# c200_rev_a.net
KiCad netlist of a schematic drawn in EAGLE
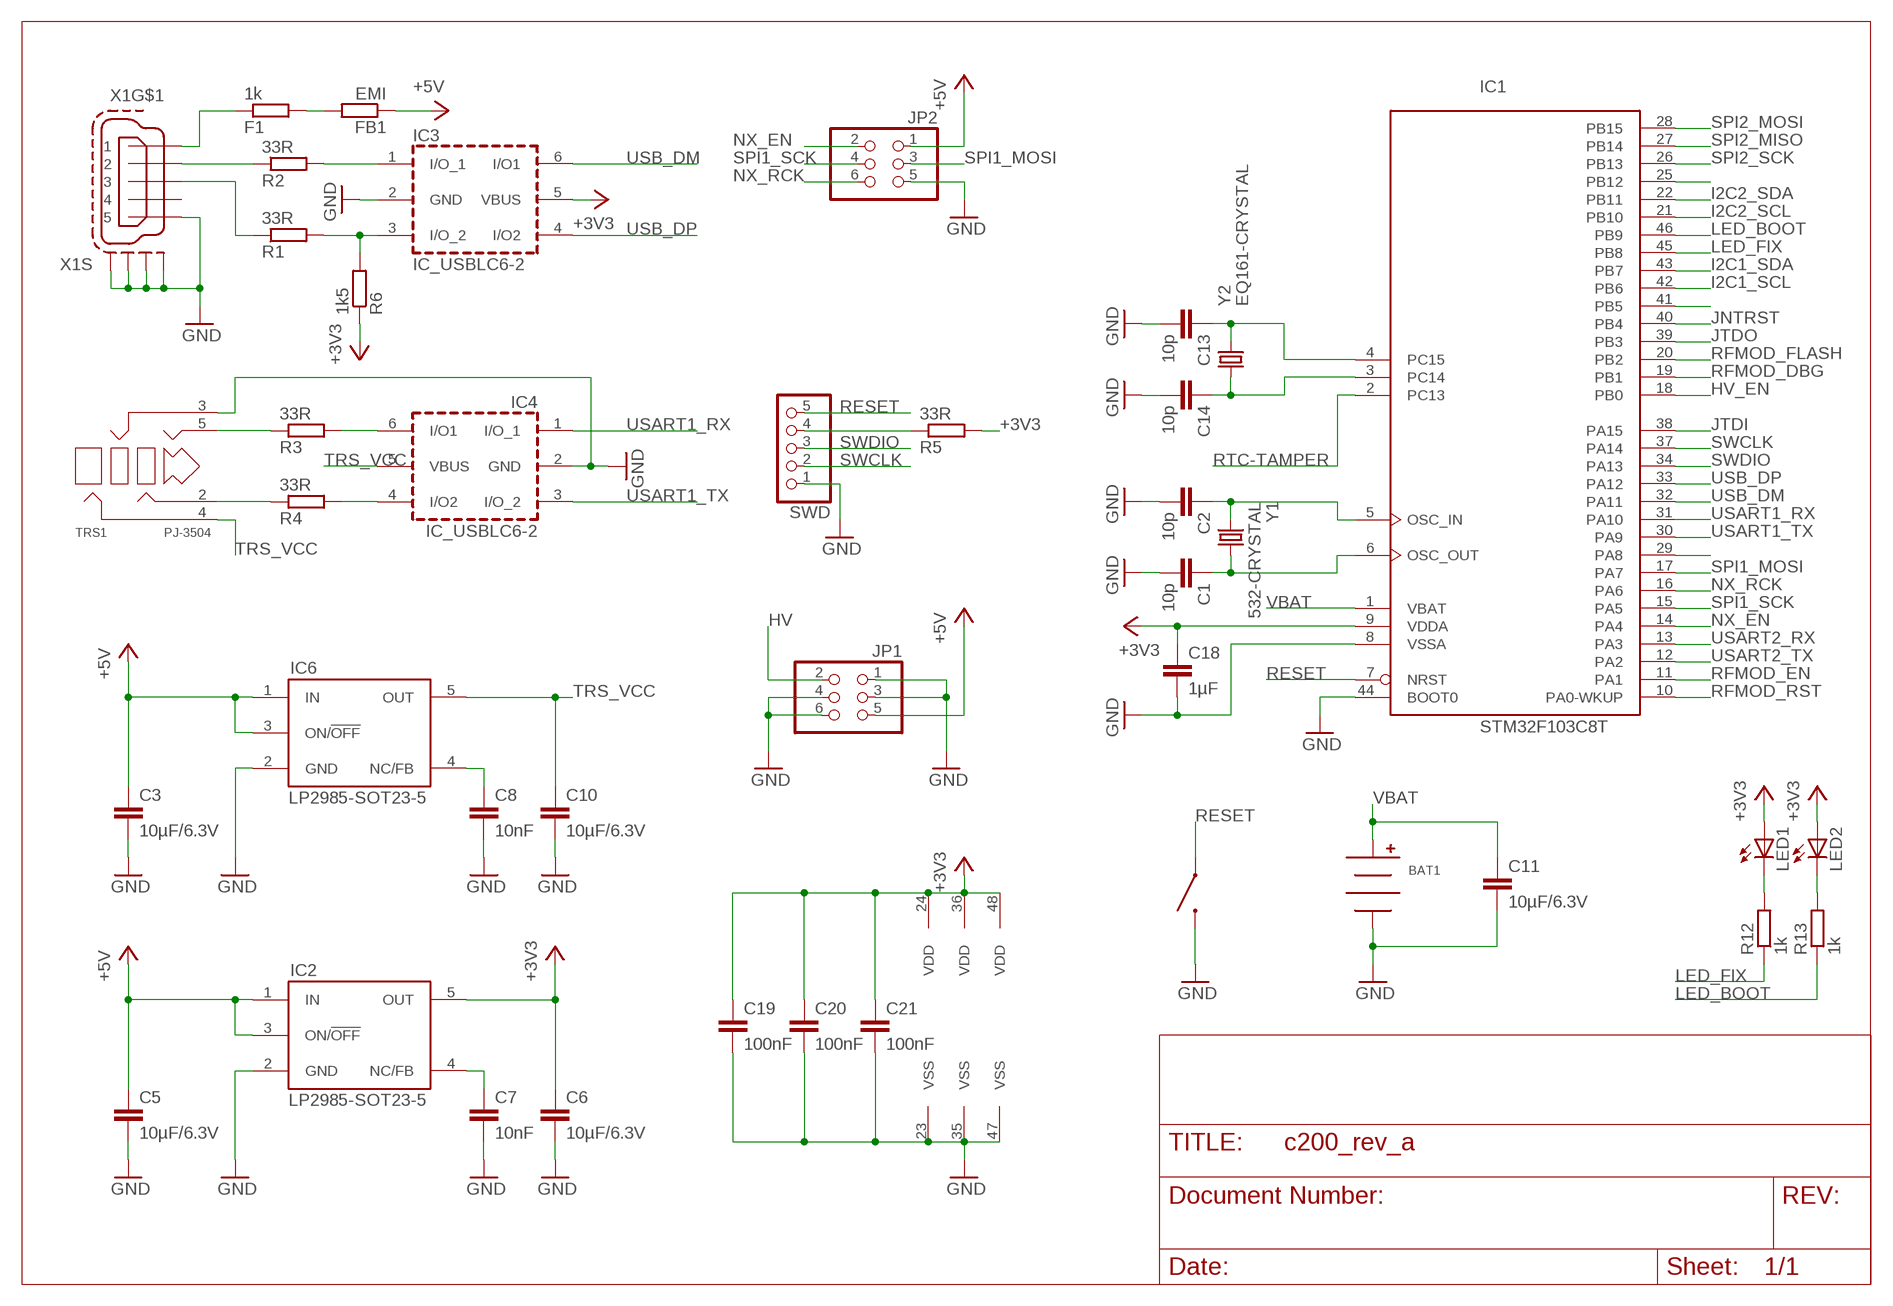
[diagram p0: schematic, sheet 1, part 1 of 2]
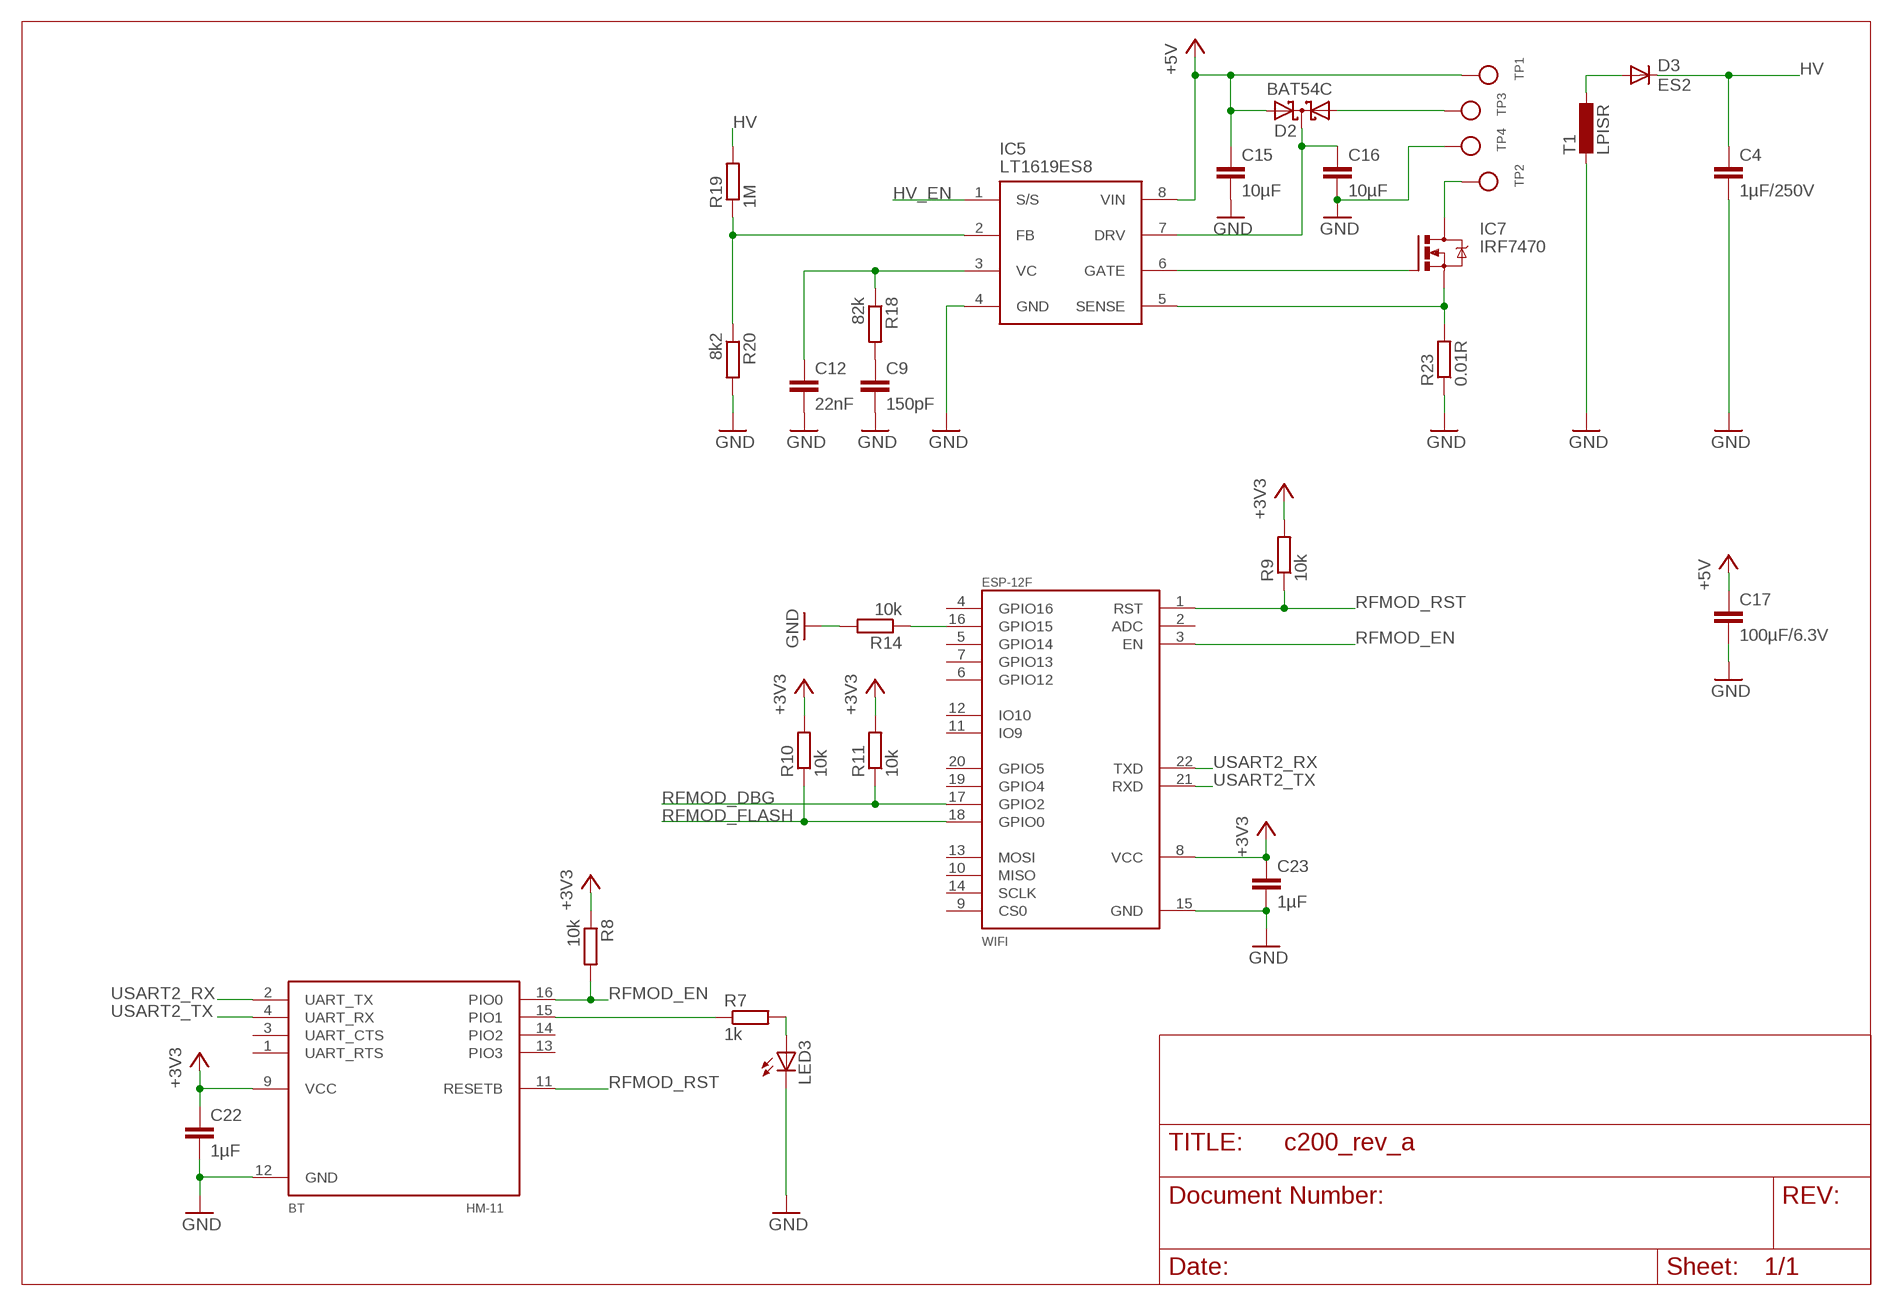
[diagram p1: schematic, sheet 1, part 2 of 2]

(export (version "E")
  (design (tool "Eeschema 10.0.6"))
  (components
    (comp (ref "BAT1")
      (value "CR1220-HOLDER")
      (footprint "eagle-import:HARWIN-CR1220")
      (libsource (lib "eagle-import") (part "CR1220-HOLDER"))
    )
    (comp (ref "BT")
      (value "HM-11")
      (footprint "eagle-import:HM-11")
      (libsource (lib "eagle-import") (part "HM-11"))
    )
    (comp (ref "C1")
      (value "10p")
      (footprint "eagle-import:C0603")
      (libsource (lib "eagle-import") (part "C-EUC0603"))
    )
    (comp (ref "C2")
      (value "10p")
      (footprint "eagle-import:C0603")
      (libsource (lib "eagle-import") (part "C-EUC0603"))
    )
    (comp (ref "C3")
      (value "10µF/6.3V")
      (footprint "eagle-import:C0603")
      (libsource (lib "eagle-import") (part "C-EUC0603"))
    )
    (comp (ref "C4")
      (value "1µF/250V")
      (footprint "eagle-import:C2220K")
      (libsource (lib "eagle-import") (part "C-EUC2220K"))
    )
    (comp (ref "C5")
      (value "10µF/6.3V")
      (footprint "eagle-import:C0603")
      (libsource (lib "eagle-import") (part "C-EUC0603"))
    )
    (comp (ref "C6")
      (value "10µF/6.3V")
      (footprint "eagle-import:C0603")
      (libsource (lib "eagle-import") (part "C-EUC0603"))
    )
    (comp (ref "C7")
      (value "10nF")
      (footprint "eagle-import:C0603")
      (libsource (lib "eagle-import") (part "C-EUC0603"))
    )
    (comp (ref "C8")
      (value "10nF")
      (footprint "eagle-import:C0603")
      (libsource (lib "eagle-import") (part "C-EUC0603"))
    )
    (comp (ref "C9")
      (value "150pF")
      (footprint "eagle-import:C0603")
      (libsource (lib "eagle-import") (part "C-EUC0603"))
    )
    (comp (ref "C10")
      (value "10µF/6.3V")
      (footprint "eagle-import:C0603")
      (libsource (lib "eagle-import") (part "C-EUC0603"))
    )
    (comp (ref "C11")
      (value "10µF/6.3V")
      (footprint "eagle-import:C0603")
      (libsource (lib "eagle-import") (part "C-EUC0603"))
    )
    (comp (ref "C12")
      (value "22nF")
      (footprint "eagle-import:C0603")
      (libsource (lib "eagle-import") (part "C-EUC0603"))
    )
    (comp (ref "C13")
      (value "10p")
      (footprint "eagle-import:C0603")
      (libsource (lib "eagle-import") (part "C-EUC0603"))
    )
    (comp (ref "C14")
      (value "10p")
      (footprint "eagle-import:C0603")
      (libsource (lib "eagle-import") (part "C-EUC0603"))
    )
    (comp (ref "C15")
      (value "10µF")
      (footprint "eagle-import:C0603")
      (libsource (lib "eagle-import") (part "C-EUC0603"))
    )
    (comp (ref "C16")
      (value "10µF")
      (footprint "eagle-import:C0603")
      (libsource (lib "eagle-import") (part "C-EUC0603"))
    )
    (comp (ref "C17")
      (value "100µF/6.3V")
      (footprint "eagle-import:C1210")
      (libsource (lib "eagle-import") (part "C-EUC1210"))
    )
    (comp (ref "C18")
      (value "1µF")
      (footprint "eagle-import:C0603")
      (libsource (lib "eagle-import") (part "C-EUC0603"))
    )
    (comp (ref "C19")
      (value "100nF")
      (footprint "eagle-import:C0603")
      (libsource (lib "eagle-import") (part "C-EUC0603"))
    )
    (comp (ref "C20")
      (value "100nF")
      (footprint "eagle-import:C0603")
      (libsource (lib "eagle-import") (part "C-EUC0603"))
    )
    (comp (ref "C21")
      (value "100nF")
      (footprint "eagle-import:C0603")
      (libsource (lib "eagle-import") (part "C-EUC0603"))
    )
    (comp (ref "C22")
      (value "1µF")
      (footprint "eagle-import:C0603")
      (libsource (lib "eagle-import") (part "C-EUC0603"))
    )
    (comp (ref "C23")
      (value "1µF")
      (footprint "eagle-import:C0603")
      (libsource (lib "eagle-import") (part "C-EUC0603"))
    )
    (comp (ref "D2")
      (value "BAT54C")
      (footprint "eagle-import:SOT23")
      (libsource (lib "eagle-import") (part "BAT54C"))
    )
    (comp (ref "D3")
      (value "ES2")
      (footprint "eagle-import:DO-214AA")
      (libsource (lib "eagle-import") (part "ES2"))
    )
    (comp (ref "F1")
      (value "1k")
      (footprint "eagle-import:R0603")
      (libsource (lib "eagle-import") (part "R-EU_R0603"))
    )
    (comp (ref "FB1")
      (value "EMI")
      (footprint "eagle-import:R0603")
      (libsource (lib "eagle-import") (part "R-EU_R0603"))
    )
    (comp (ref "IC1")
      (value "STM32F103C8T")
      (footprint "eagle-import:LQFP48")
      (libsource (lib "eagle-import") (part "STM32F103CT8"))
    )
    (comp (ref "IC2")
      (value "LP2985-SOT23-5")
      (footprint "eagle-import:SOT23-5")
      (libsource (lib "eagle-import") (part "LP2985-SOT23-5"))
    )
    (comp (ref "IC3")
      (value "IC_USBLC6-2")
      (footprint "eagle-import:SOT-23-6L")
      (libsource (lib "eagle-import") (part "IC_USBLC6-2"))
    )
    (comp (ref "IC4")
      (value "IC_USBLC6-2")
      (footprint "eagle-import:SOT-23-6L")
      (libsource (lib "eagle-import") (part "IC_USBLC6-2"))
    )
    (comp (ref "IC5")
      (value "LT1619ES8")
      (footprint "eagle-import:SO8")
      (libsource (lib "eagle-import") (part "LT1619ES8"))
    )
    (comp (ref "IC6")
      (value "LP2985-SOT23-5")
      (footprint "eagle-import:SOT23-5")
      (libsource (lib "eagle-import") (part "LP2985-SOT23-5"))
    )
    (comp (ref "IC7")
      (value "IRF7470")
      (footprint "eagle-import:SO8")
      (libsource (lib "eagle-import") (part "IRF7470"))
    )
    (comp (ref "ISP")
      (value "TACT-SWITCH-40-40")
      (footprint "eagle-import:40-40")
      (libsource (lib "eagle-import") (part "TACT-SWITCH-40-40"))
    )
    (comp (ref "JP1")
      (value "PINHD-2X3_2.54-SMD")
      (footprint "eagle-import:2X03SMD")
      (libsource (lib "eagle-import") (part "PINHD-2X3_2.54-SMD"))
    )
    (comp (ref "JP2")
      (value "PINHD-2X3_2.54-SMD")
      (footprint "eagle-import:2X03SMD")
      (libsource (lib "eagle-import") (part "PINHD-2X3_2.54-SMD"))
    )
    (comp (ref "LED1")
      (value "LEDCHIP-LED0603")
      (footprint "eagle-import:CHIP-LED0603")
      (libsource (lib "eagle-import") (part "LEDCHIP-LED0603"))
    )
    (comp (ref "LED2")
      (value "LEDCHIP-LED0603")
      (footprint "eagle-import:CHIP-LED0603")
      (libsource (lib "eagle-import") (part "LEDCHIP-LED0603"))
    )
    (comp (ref "LED3")
      (value "LEDCHIP-LED0603")
      (footprint "eagle-import:CHIP-LED0603")
      (libsource (lib "eagle-import") (part "LEDCHIP-LED0603"))
    )
    (comp (ref "R1")
      (value "33R")
      (footprint "eagle-import:R0603")
      (libsource (lib "eagle-import") (part "R-EU_R0603"))
    )
    (comp (ref "R2")
      (value "33R")
      (footprint "eagle-import:R0603")
      (libsource (lib "eagle-import") (part "R-EU_R0603"))
    )
    (comp (ref "R3")
      (value "33R")
      (footprint "eagle-import:R0603")
      (libsource (lib "eagle-import") (part "R-EU_R0603"))
    )
    (comp (ref "R4")
      (value "33R")
      (footprint "eagle-import:R0603")
      (libsource (lib "eagle-import") (part "R-EU_R0603"))
    )
    (comp (ref "R5")
      (value "33R")
      (footprint "eagle-import:R0603")
      (libsource (lib "eagle-import") (part "R-EU_R0603"))
    )
    (comp (ref "R6")
      (value "1k5")
      (footprint "eagle-import:R0603")
      (libsource (lib "eagle-import") (part "R-EU_R0603"))
    )
    (comp (ref "R7")
      (value "1k")
      (footprint "eagle-import:R0603")
      (libsource (lib "eagle-import") (part "R-EU_R0603"))
    )
    (comp (ref "R8")
      (value "10k")
      (footprint "eagle-import:R0603")
      (libsource (lib "eagle-import") (part "R-EU_R0603"))
    )
    (comp (ref "R9")
      (value "10k")
      (footprint "eagle-import:R0603")
      (libsource (lib "eagle-import") (part "R-EU_R0603"))
    )
    (comp (ref "R10")
      (value "10k")
      (footprint "eagle-import:R0603")
      (libsource (lib "eagle-import") (part "R-EU_R0603"))
    )
    (comp (ref "R11")
      (value "10k")
      (footprint "eagle-import:R0603")
      (libsource (lib "eagle-import") (part "R-EU_R0603"))
    )
    (comp (ref "R12")
      (value "1k")
      (footprint "eagle-import:R0603")
      (libsource (lib "eagle-import") (part "R-EU_R0603"))
    )
    (comp (ref "R13")
      (value "1k")
      (footprint "eagle-import:R0603")
      (libsource (lib "eagle-import") (part "R-EU_R0603"))
    )
    (comp (ref "R14")
      (value "10k")
      (footprint "eagle-import:R0603")
      (libsource (lib "eagle-import") (part "R-EU_R0603"))
    )
    (comp (ref "R18")
      (value "82k")
      (footprint "eagle-import:R0603")
      (libsource (lib "eagle-import") (part "R-EU_R0603"))
    )
    (comp (ref "R19")
      (value "1M")
      (footprint "eagle-import:M1206")
      (libsource (lib "eagle-import") (part "R-EU_M1206"))
    )
    (comp (ref "R20")
      (value "8k2")
      (footprint "eagle-import:R0603")
      (libsource (lib "eagle-import") (part "R-EU_R0603"))
    )
    (comp (ref "R23")
      (value "0.01R")
      (footprint "eagle-import:R1206")
      (libsource (lib "eagle-import") (part "R-EU_R1206"))
    )
    (comp (ref "SWD")
      (value "HEADER-1X5ROUND")
      (footprint "eagle-import:1X05_ROUND")
      (libsource (lib "eagle-import") (part "HEADER-1X5ROUND"))
    )
    (comp (ref "T1")
      (value "LPISR")
      (footprint "eagle-import:PISR")
      (libsource (lib "eagle-import") (part "LPISR"))
    )
    (comp (ref "TP1")
      (value "TESTPOINTROUND2MM")
      (footprint "eagle-import:TESTPOINT_ROUND_2MM")
      (libsource (lib "eagle-import") (part "TESTPOINTROUND2MM"))
    )
    (comp (ref "TP2")
      (value "TESTPOINTROUND2MM")
      (footprint "eagle-import:TESTPOINT_ROUND_2MM")
      (libsource (lib "eagle-import") (part "TESTPOINTROUND2MM"))
    )
    (comp (ref "TP3")
      (value "TESTPOINTROUND2MM")
      (footprint "eagle-import:TESTPOINT_ROUND_2MM")
      (libsource (lib "eagle-import") (part "TESTPOINTROUND2MM"))
    )
    (comp (ref "TP4")
      (value "TESTPOINTROUND2MM")
      (footprint "eagle-import:TESTPOINT_ROUND_2MM")
      (libsource (lib "eagle-import") (part "TESTPOINTROUND2MM"))
    )
    (comp (ref "TRS1")
      (value "PJ-3504")
      (footprint "eagle-import:YD-PJ-3504")
      (libsource (lib "eagle-import") (part "PJ-3504"))
    )
    (comp (ref "WIFI")
      (value "ESP-12F")
      (footprint "eagle-import:ESP-12F")
      (libsource (lib "eagle-import") (part "ESP-12F"))
    )
    (comp (ref "X1")
      (value "MINI-USB-SCHIELD-32005-201")
      (footprint "eagle-import:32005-201")
      (libsource (lib "eagle-import") (part "MINI-USB-SCHIELD-32005-201"))
    )
    (comp (ref "Y1")
      (value "532-CRYSTAL")
      (footprint "eagle-import:2PIN50X32")
      (libsource (lib "eagle-import") (part "532-CRYSTAL"))
    )
    (comp (ref "Y2")
      (value "EQ161-CRYSTAL")
      (footprint "eagle-import:EQ161")
      (libsource (lib "eagle-import") (part "EQ161-CRYSTAL"))
    )
  )
  (nets
    (net (code "1") (name "+3V3") (class "Default")
      (node (ref "BT") (pin "9") (pinfunction "VCC_9") (pintype "bidirectional"))
      (node (ref "C18") (pin "1") (pinfunction "1_1") (pintype "passive"))
      (node (ref "C19") (pin "1") (pinfunction "1_1") (pintype "passive"))
      (node (ref "C20") (pin "1") (pinfunction "1_1") (pintype "passive"))
      (node (ref "C21") (pin "1") (pinfunction "1_1") (pintype "passive"))
      (node (ref "C22") (pin "1") (pinfunction "1_1") (pintype "passive"))
      (node (ref "C23") (pin "1") (pinfunction "1_1") (pintype "passive"))
      (node (ref "C6") (pin "1") (pinfunction "1_1") (pintype "passive"))
      (node (ref "IC1") (pin "24") (pinfunction "VDD_24") (pintype "power_in"))
      (node (ref "IC1") (pin "36") (pinfunction "VDD_36") (pintype "power_in"))
      (node (ref "IC1") (pin "48") (pinfunction "VDD_48") (pintype "power_in"))
      (node (ref "IC1") (pin "9") (pinfunction "VDDA_9") (pintype "power_in"))
      (node (ref "IC2") (pin "5") (pinfunction "OUT_5") (pintype "bidirectional"))
      (node (ref "IC3") (pin "5") (pinfunction "VBUS_5") (pintype "bidirectional"))
      (node (ref "LED1") (pin "A") (pinfunction "A_A") (pintype "passive"))
      (node (ref "LED2") (pin "A") (pinfunction "A_A") (pintype "passive"))
      (node (ref "R10") (pin "2") (pinfunction "2_2") (pintype "passive"))
      (node (ref "R11") (pin "2") (pinfunction "2_2") (pintype "passive"))
      (node (ref "R5") (pin "2") (pinfunction "2_2") (pintype "passive"))
      (node (ref "R6") (pin "1") (pinfunction "1_1") (pintype "passive"))
      (node (ref "R8") (pin "1") (pinfunction "1_1") (pintype "passive"))
      (node (ref "R9") (pin "2") (pinfunction "2_2") (pintype "passive"))
      (node (ref "WIFI") (pin "8") (pinfunction "VCC_8") (pintype "bidirectional"))
    )
    (net (code "2") (name "+5V") (class "Default")
      (node (ref "C15") (pin "1") (pinfunction "1_1") (pintype "passive"))
      (node (ref "C17") (pin "1") (pinfunction "1_1") (pintype "passive"))
      (node (ref "C3") (pin "1") (pinfunction "1_1") (pintype "passive"))
      (node (ref "C5") (pin "1") (pinfunction "1_1") (pintype "passive"))
      (node (ref "D2") (pin "2") (pinfunction "A2_2") (pintype "passive"))
      (node (ref "FB1") (pin "1") (pinfunction "1_1") (pintype "passive"))
      (node (ref "IC2") (pin "1") (pinfunction "IN_1") (pintype "bidirectional"))
      (node (ref "IC2") (pin "3") (pinfunction "ON/~{OFF}_3") (pintype "bidirectional"))
      (node (ref "IC5") (pin "8") (pinfunction "VIN_8") (pintype "bidirectional"))
      (node (ref "IC6") (pin "1") (pinfunction "IN_1") (pintype "bidirectional"))
      (node (ref "IC6") (pin "3") (pinfunction "ON/~{OFF}_3") (pintype "bidirectional"))
      (node (ref "JP1") (pin "5") (pinfunction "5_5") (pintype "passive"))
      (node (ref "JP2") (pin "1") (pinfunction "1_1") (pintype "passive"))
      (node (ref "TP1") (pin "P$1") (pinfunction "P$1_P$1") (pintype "bidirectional"))
    )
    (net (code "3") (name "/HV") (class "Default")
      (node (ref "C4") (pin "1") (pinfunction "1_1") (pintype "passive"))
      (node (ref "D3") (pin "C") (pinfunction "C_C") (pintype "passive"))
      (node (ref "JP1") (pin "2") (pinfunction "2_2") (pintype "passive"))
      (node (ref "R19") (pin "2") (pinfunction "2_2") (pintype "passive"))
    )
    (net (code "4") (name "/HV_EN") (class "Default")
      (node (ref "IC1") (pin "18") (pinfunction "PB0_18") (pintype "bidirectional"))
      (node (ref "IC5") (pin "1") (pinfunction "S/S_1") (pintype "bidirectional"))
    )
    (net (code "5") (name "/I2C1_SCL") (class "Default")
      (node (ref "IC1") (pin "42") (pinfunction "PB6_42") (pintype "bidirectional"))
    )
    (net (code "6") (name "/I2C1_SDA") (class "Default")
      (node (ref "IC1") (pin "43") (pinfunction "PB7_43") (pintype "bidirectional"))
    )
    (net (code "7") (name "/I2C2_SCL") (class "Default")
      (node (ref "IC1") (pin "21") (pinfunction "PB10_21") (pintype "bidirectional"))
    )
    (net (code "8") (name "/I2C2_SDA") (class "Default")
      (node (ref "IC1") (pin "22") (pinfunction "PB11_22") (pintype "bidirectional"))
    )
    (net (code "9") (name "/JNTRST") (class "Default")
      (node (ref "IC1") (pin "40") (pinfunction "PB4_40") (pintype "bidirectional"))
    )
    (net (code "10") (name "/JTDI") (class "Default")
      (node (ref "IC1") (pin "38") (pinfunction "PA15_38") (pintype "bidirectional"))
    )
    (net (code "11") (name "/JTDO") (class "Default")
      (node (ref "IC1") (pin "39") (pinfunction "PB3_39") (pintype "bidirectional"))
    )
    (net (code "12") (name "/LED_BOOT") (class "Default")
      (node (ref "IC1") (pin "46") (pinfunction "PB9_46") (pintype "bidirectional"))
      (node (ref "R13") (pin "1") (pinfunction "1_1") (pintype "passive"))
    )
    (net (code "13") (name "/LED_FIX") (class "Default")
      (node (ref "IC1") (pin "45") (pinfunction "PB8_45") (pintype "bidirectional"))
      (node (ref "R12") (pin "1") (pinfunction "1_1") (pintype "passive"))
    )
    (net (code "14") (name "/NX_EN") (class "Default")
      (node (ref "IC1") (pin "14") (pinfunction "PA4_14") (pintype "bidirectional"))
      (node (ref "JP2") (pin "2") (pinfunction "2_2") (pintype "passive"))
    )
    (net (code "15") (name "/NX_RCK") (class "Default")
      (node (ref "IC1") (pin "16") (pinfunction "PA6_16") (pintype "bidirectional"))
      (node (ref "JP2") (pin "6") (pinfunction "6_6") (pintype "passive"))
    )
    (net (code "16") (name "/RESET") (class "Default")
      (node (ref "IC1") (pin "7") (pinfunction "NRST_7") (pintype "bidirectional"))
      (node (ref "ISP") (pin "3") (pinfunction "P$2_3") (pintype "bidirectional"))
      (node (ref "ISP") (pin "4") (pinfunction "P$2_4") (pintype "bidirectional"))
      (node (ref "SWD") (pin "5") (pinfunction "5_5") (pintype "passive"))
    )
    (net (code "17") (name "/RFMOD_DBG") (class "Default")
      (node (ref "IC1") (pin "19") (pinfunction "PB1_19") (pintype "bidirectional"))
      (node (ref "R11") (pin "1") (pinfunction "1_1") (pintype "passive"))
      (node (ref "WIFI") (pin "17") (pinfunction "GPIO2_17") (pintype "bidirectional"))
    )
    (net (code "18") (name "/RFMOD_EN") (class "Default")
      (node (ref "BT") (pin "16") (pinfunction "PIO0_16") (pintype "bidirectional"))
      (node (ref "IC1") (pin "11") (pinfunction "PA1_11") (pintype "bidirectional"))
      (node (ref "R8") (pin "2") (pinfunction "2_2") (pintype "passive"))
      (node (ref "WIFI") (pin "3") (pinfunction "EN_3") (pintype "bidirectional"))
    )
    (net (code "19") (name "/RFMOD_FLASH") (class "Default")
      (node (ref "IC1") (pin "20") (pinfunction "PB2_20") (pintype "bidirectional"))
      (node (ref "R10") (pin "1") (pinfunction "1_1") (pintype "passive"))
      (node (ref "WIFI") (pin "18") (pinfunction "GPIO0_18") (pintype "bidirectional"))
    )
    (net (code "20") (name "/RFMOD_RST") (class "Default")
      (node (ref "BT") (pin "11") (pinfunction "RESETB_11") (pintype "bidirectional"))
      (node (ref "IC1") (pin "10") (pinfunction "PA0-WKUP_10") (pintype "bidirectional"))
      (node (ref "R9") (pin "1") (pinfunction "1_1") (pintype "passive"))
      (node (ref "WIFI") (pin "1") (pinfunction "RST_1") (pintype "bidirectional"))
    )
    (net (code "21") (name "/RTC-TAMPER") (class "Default")
      (node (ref "IC1") (pin "2") (pinfunction "PC13_2") (pintype "bidirectional"))
    )
    (net (code "22") (name "/SPI1_MOSI") (class "Default")
      (node (ref "IC1") (pin "17") (pinfunction "PA7_17") (pintype "bidirectional"))
      (node (ref "JP2") (pin "3") (pinfunction "3_3") (pintype "passive"))
    )
    (net (code "23") (name "/SPI1_SCK") (class "Default")
      (node (ref "IC1") (pin "15") (pinfunction "PA5_15") (pintype "bidirectional"))
      (node (ref "JP2") (pin "4") (pinfunction "4_4") (pintype "passive"))
    )
    (net (code "24") (name "/SPI2_MISO") (class "Default")
      (node (ref "IC1") (pin "27") (pinfunction "PB14_27") (pintype "bidirectional"))
    )
    (net (code "25") (name "/SPI2_MOSI") (class "Default")
      (node (ref "IC1") (pin "28") (pinfunction "PB15_28") (pintype "bidirectional"))
    )
    (net (code "26") (name "/SPI2_SCK") (class "Default")
      (node (ref "IC1") (pin "26") (pinfunction "PB13_26") (pintype "bidirectional"))
    )
    (net (code "27") (name "/SWCLK") (class "Default")
      (node (ref "IC1") (pin "37") (pinfunction "PA14_37") (pintype "bidirectional"))
      (node (ref "SWD") (pin "2") (pinfunction "2_2") (pintype "passive"))
    )
    (net (code "28") (name "/SWDIO") (class "Default")
      (node (ref "IC1") (pin "34") (pinfunction "PA13_34") (pintype "bidirectional"))
      (node (ref "SWD") (pin "3") (pinfunction "3_3") (pintype "passive"))
    )
    (net (code "29") (name "/TRS_VCC") (class "Default")
      (node (ref "C10") (pin "1") (pinfunction "1_1") (pintype "passive"))
      (node (ref "IC4") (pin "5") (pinfunction "VBUS_5") (pintype "bidirectional"))
      (node (ref "IC6") (pin "5") (pinfunction "OUT_5") (pintype "bidirectional"))
      (node (ref "TRS1") (pin "4") (pinfunction "4_4") (pintype "bidirectional"))
    )
    (net (code "30") (name "/USART1_RX") (class "Default")
      (node (ref "IC1") (pin "31") (pinfunction "PA10_31") (pintype "bidirectional"))
      (node (ref "IC4") (pin "1") (pinfunction "I/O_1_1") (pintype "bidirectional"))
    )
    (net (code "31") (name "/USART1_TX") (class "Default")
      (node (ref "IC1") (pin "30") (pinfunction "PA9_30") (pintype "bidirectional"))
      (node (ref "IC4") (pin "3") (pinfunction "I/O_2_3") (pintype "bidirectional"))
    )
    (net (code "32") (name "/USART2_RX") (class "Default")
      (node (ref "BT") (pin "2") (pinfunction "UART_TX_2") (pintype "bidirectional"))
      (node (ref "IC1") (pin "13") (pinfunction "PA3_13") (pintype "bidirectional"))
      (node (ref "WIFI") (pin "22") (pinfunction "TXD_22") (pintype "bidirectional"))
    )
    (net (code "33") (name "/USART2_TX") (class "Default")
      (node (ref "BT") (pin "4") (pinfunction "UART_RX_4") (pintype "bidirectional"))
      (node (ref "IC1") (pin "12") (pinfunction "PA2_12") (pintype "bidirectional"))
      (node (ref "WIFI") (pin "21") (pinfunction "RXD_21") (pintype "bidirectional"))
    )
    (net (code "34") (name "/USB_DM") (class "Default")
      (node (ref "IC1") (pin "32") (pinfunction "PA11_32") (pintype "bidirectional"))
      (node (ref "IC3") (pin "6") (pinfunction "I/O1_6") (pintype "bidirectional"))
    )
    (net (code "35") (name "/USB_DP") (class "Default")
      (node (ref "IC1") (pin "33") (pinfunction "PA12_33") (pintype "bidirectional"))
      (node (ref "IC3") (pin "4") (pinfunction "I/O2_4") (pintype "bidirectional"))
    )
    (net (code "36") (name "/VBAT") (class "Default")
      (node (ref "BAT1") (pin "POS") (pinfunction "POS_POS") (pintype "bidirectional"))
      (node (ref "C11") (pin "1") (pinfunction "1_1") (pintype "passive"))
      (node (ref "IC1") (pin "1") (pinfunction "VBAT_1") (pintype "power_in"))
    )
    (net (code "37") (name "GND") (class "Default")
      (node (ref "BAT1") (pin "NEG") (pinfunction "NEG_NEG") (pintype "bidirectional"))
      (node (ref "BT") (pin "12") (pinfunction "GND_12") (pintype "bidirectional"))
      (node (ref "C1") (pin "2") (pinfunction "2_2") (pintype "passive"))
      (node (ref "C10") (pin "2") (pinfunction "2_2") (pintype "passive"))
      (node (ref "C11") (pin "2") (pinfunction "2_2") (pintype "passive"))
      (node (ref "C12") (pin "2") (pinfunction "2_2") (pintype "passive"))
      (node (ref "C13") (pin "2") (pinfunction "2_2") (pintype "passive"))
      (node (ref "C14") (pin "2") (pinfunction "2_2") (pintype "passive"))
      (node (ref "C15") (pin "2") (pinfunction "2_2") (pintype "passive"))
      (node (ref "C16") (pin "2") (pinfunction "2_2") (pintype "passive"))
      (node (ref "C17") (pin "2") (pinfunction "2_2") (pintype "passive"))
      (node (ref "C18") (pin "2") (pinfunction "2_2") (pintype "passive"))
      (node (ref "C19") (pin "2") (pinfunction "2_2") (pintype "passive"))
      (node (ref "C2") (pin "2") (pinfunction "2_2") (pintype "passive"))
      (node (ref "C20") (pin "2") (pinfunction "2_2") (pintype "passive"))
      (node (ref "C21") (pin "2") (pinfunction "2_2") (pintype "passive"))
      (node (ref "C22") (pin "2") (pinfunction "2_2") (pintype "passive"))
      (node (ref "C23") (pin "2") (pinfunction "2_2") (pintype "passive"))
      (node (ref "C3") (pin "2") (pinfunction "2_2") (pintype "passive"))
      (node (ref "C4") (pin "2") (pinfunction "2_2") (pintype "passive"))
      (node (ref "C5") (pin "2") (pinfunction "2_2") (pintype "passive"))
      (node (ref "C6") (pin "2") (pinfunction "2_2") (pintype "passive"))
      (node (ref "C7") (pin "2") (pinfunction "2_2") (pintype "passive"))
      (node (ref "C8") (pin "2") (pinfunction "2_2") (pintype "passive"))
      (node (ref "C9") (pin "2") (pinfunction "2_2") (pintype "passive"))
      (node (ref "IC1") (pin "23") (pinfunction "VSS_23") (pintype "power_in"))
      (node (ref "IC1") (pin "35") (pinfunction "VSS_35") (pintype "power_in"))
      (node (ref "IC1") (pin "44") (pinfunction "BOOT0_44") (pintype "input"))
      (node (ref "IC1") (pin "47") (pinfunction "VSS_47") (pintype "power_in"))
      (node (ref "IC1") (pin "8") (pinfunction "VSSA_8") (pintype "power_in"))
      (node (ref "IC2") (pin "2") (pinfunction "GND_2") (pintype "bidirectional"))
      (node (ref "IC3") (pin "2") (pinfunction "GND_2") (pintype "bidirectional"))
      (node (ref "IC4") (pin "2") (pinfunction "GND_2") (pintype "bidirectional"))
      (node (ref "IC5") (pin "4") (pinfunction "GND_4") (pintype "bidirectional"))
      (node (ref "IC6") (pin "2") (pinfunction "GND_2") (pintype "bidirectional"))
      (node (ref "ISP") (pin "1") (pinfunction "P$1_1") (pintype "bidirectional"))
      (node (ref "ISP") (pin "2") (pinfunction "P$1_2") (pintype "bidirectional"))
      (node (ref "JP1") (pin "1") (pinfunction "1_1") (pintype "passive"))
      (node (ref "JP1") (pin "3") (pinfunction "3_3") (pintype "passive"))
      (node (ref "JP1") (pin "4") (pinfunction "4_4") (pintype "passive"))
      (node (ref "JP1") (pin "6") (pinfunction "6_6") (pintype "passive"))
      (node (ref "JP2") (pin "5") (pinfunction "5_5") (pintype "passive"))
      (node (ref "LED3") (pin "C") (pinfunction "C_C") (pintype "passive"))
      (node (ref "R14") (pin "2") (pinfunction "2_2") (pintype "passive"))
      (node (ref "R20") (pin "2") (pinfunction "2_2") (pintype "passive"))
      (node (ref "R23") (pin "1") (pinfunction "1_1") (pintype "passive"))
      (node (ref "SWD") (pin "1") (pinfunction "1_1") (pintype "passive"))
      (node (ref "T1") (pin "P$2") (pinfunction "2_P$2") (pintype "passive"))
      (node (ref "TP4") (pin "P$1") (pinfunction "P$1_P$1") (pintype "bidirectional"))
      (node (ref "TRS1") (pin "3") (pinfunction "3_3") (pintype "bidirectional"))
      (node (ref "WIFI") (pin "15") (pinfunction "GND_15") (pintype "bidirectional"))
      (node (ref "X1") (pin "5") (pinfunction "5_5") (pintype "passive"))
      (node (ref "X1") (pin "M1") (pinfunction "S1_M1") (pintype "passive"))
      (node (ref "X1") (pin "M2") (pinfunction "S2_M2") (pintype "passive"))
      (node (ref "X1") (pin "M3") (pinfunction "S3_M3") (pintype "passive"))
      (node (ref "X1") (pin "M4") (pinfunction "S4_M4") (pintype "passive"))
    )
    (net (code "38") (name "Net-(BT-PIO1)") (class "Default")
      (node (ref "BT") (pin "15") (pinfunction "PIO1_15") (pintype "bidirectional"))
      (node (ref "R7") (pin "1") (pinfunction "1_1") (pintype "passive"))
    )
    (net (code "39") (name "Net-(C9-Pad1)") (class "Default")
      (node (ref "C9") (pin "1") (pinfunction "1_1") (pintype "passive"))
      (node (ref "R18") (pin "2") (pinfunction "2_2") (pintype "passive"))
    )
    (net (code "40") (name "Net-(D2-A1)") (class "Default")
      (node (ref "D2") (pin "1") (pinfunction "A1_1") (pintype "passive"))
      (node (ref "TP3") (pin "P$1") (pinfunction "P$1_P$1") (pintype "bidirectional"))
    )
    (net (code "41") (name "Net-(D2-CC)") (class "Default")
      (node (ref "C16") (pin "1") (pinfunction "1_1") (pintype "passive"))
      (node (ref "D2") (pin "3") (pinfunction "CC_3") (pintype "passive"))
      (node (ref "IC5") (pin "7") (pinfunction "DRV_7") (pintype "bidirectional"))
    )
    (net (code "42") (name "Net-(F1-Pad1)") (class "Default")
      (node (ref "F1") (pin "1") (pinfunction "1_1") (pintype "passive"))
      (node (ref "X1") (pin "1") (pinfunction "1_1") (pintype "passive"))
    )
    (net (code "43") (name "Net-(F1-Pad2)") (class "Default")
      (node (ref "F1") (pin "2") (pinfunction "2_2") (pintype "passive"))
      (node (ref "FB1") (pin "2") (pinfunction "2_2") (pintype "passive"))
    )
    (net (code "44") (name "Net-(IC1A-OSC_IN)") (class "Default")
      (node (ref "C2") (pin "1") (pinfunction "1_1") (pintype "passive"))
      (node (ref "IC1") (pin "5") (pinfunction "OSC_IN_5") (pintype "bidirectional"))
      (node (ref "Y1") (pin "P$2") (pinfunction "2_P$2") (pintype "passive"))
    )
    (net (code "45") (name "Net-(IC1A-OSC_OUT)") (class "Default")
      (node (ref "C1") (pin "1") (pinfunction "1_1") (pintype "passive"))
      (node (ref "IC1") (pin "6") (pinfunction "OSC_OUT_6") (pintype "bidirectional"))
      (node (ref "Y1") (pin "P$1") (pinfunction "1_P$1") (pintype "passive"))
    )
    (net (code "46") (name "Net-(IC1A-PC14)") (class "Default")
      (node (ref "C14") (pin "1") (pinfunction "1_1") (pintype "passive"))
      (node (ref "IC1") (pin "3") (pinfunction "PC14_3") (pintype "bidirectional"))
      (node (ref "Y2") (pin "P$2") (pinfunction "2_P$2") (pintype "passive"))
    )
    (net (code "47") (name "Net-(IC1A-PC15)") (class "Default")
      (node (ref "C13") (pin "1") (pinfunction "1_1") (pintype "passive"))
      (node (ref "IC1") (pin "4") (pinfunction "PC15_4") (pintype "bidirectional"))
      (node (ref "Y2") (pin "P$1") (pinfunction "1_P$1") (pintype "passive"))
    )
    (net (code "48") (name "Net-(IC2-NC{slash}FB)") (class "Default")
      (node (ref "C7") (pin "1") (pinfunction "1_1") (pintype "passive"))
      (node (ref "IC2") (pin "4") (pinfunction "NC/FB_4") (pintype "bidirectional"))
    )
    (net (code "49") (name "Net-(IC3-I{slash}O_1)") (class "Default")
      (node (ref "IC3") (pin "1") (pinfunction "I/O_1_1") (pintype "bidirectional"))
      (node (ref "R2") (pin "2") (pinfunction "2_2") (pintype "passive"))
    )
    (net (code "50") (name "Net-(IC3-I{slash}O_2)") (class "Default")
      (node (ref "IC3") (pin "3") (pinfunction "I/O_2_3") (pintype "bidirectional"))
      (node (ref "R1") (pin "2") (pinfunction "2_2") (pintype "passive"))
      (node (ref "R6") (pin "2") (pinfunction "2_2") (pintype "passive"))
    )
    (net (code "51") (name "Net-(IC4-I{slash}O1)") (class "Default")
      (node (ref "IC4") (pin "6") (pinfunction "I/O1_6") (pintype "bidirectional"))
      (node (ref "R3") (pin "2") (pinfunction "2_2") (pintype "passive"))
    )
    (net (code "52") (name "Net-(IC4-I{slash}O2)") (class "Default")
      (node (ref "IC4") (pin "4") (pinfunction "I/O2_4") (pintype "bidirectional"))
      (node (ref "R4") (pin "2") (pinfunction "2_2") (pintype "passive"))
    )
    (net (code "53") (name "Net-(IC5-FB)") (class "Default")
      (node (ref "IC5") (pin "2") (pinfunction "FB_2") (pintype "bidirectional"))
      (node (ref "R19") (pin "1") (pinfunction "1_1") (pintype "passive"))
      (node (ref "R20") (pin "1") (pinfunction "1_1") (pintype "passive"))
    )
    (net (code "54") (name "Net-(IC5-GATE)") (class "Default")
      (node (ref "IC5") (pin "6") (pinfunction "GATE_6") (pintype "bidirectional"))
      (node (ref "IC7") (pin "4") (pinfunction "G_4") (pintype "passive"))
    )
    (net (code "55") (name "Net-(IC5-SENSE)") (class "Default")
      (node (ref "IC5") (pin "5") (pinfunction "SENSE_5") (pintype "bidirectional"))
      (node (ref "IC7") (pin "1") (pinfunction "S_1") (pintype "passive"))
      (node (ref "IC7") (pin "2") (pinfunction "S_2") (pintype "passive"))
      (node (ref "IC7") (pin "3") (pinfunction "S_3") (pintype "passive"))
      (node (ref "R23") (pin "2") (pinfunction "2_2") (pintype "passive"))
    )
    (net (code "56") (name "Net-(IC5-VC)") (class "Default")
      (node (ref "C12") (pin "1") (pinfunction "1_1") (pintype "passive"))
      (node (ref "IC5") (pin "3") (pinfunction "VC_3") (pintype "bidirectional"))
      (node (ref "R18") (pin "1") (pinfunction "1_1") (pintype "passive"))
    )
    (net (code "57") (name "Net-(IC6-NC{slash}FB)") (class "Default")
      (node (ref "C8") (pin "1") (pinfunction "1_1") (pintype "passive"))
      (node (ref "IC6") (pin "4") (pinfunction "NC/FB_4") (pintype "bidirectional"))
    )
    (net (code "58") (name "Net-(IC7-D-Pad5)") (class "Default")
      (node (ref "IC7") (pin "5") (pinfunction "D_5") (pintype "passive"))
      (node (ref "IC7") (pin "6") (pinfunction "D_6") (pintype "passive"))
      (node (ref "IC7") (pin "7") (pinfunction "D_7") (pintype "passive"))
      (node (ref "IC7") (pin "8") (pinfunction "D_8") (pintype "passive"))
      (node (ref "TP2") (pin "P$1") (pinfunction "P$1_P$1") (pintype "bidirectional"))
    )
    (net (code "59") (name "Net-(LED1-PadC)") (class "Default")
      (node (ref "LED1") (pin "C") (pinfunction "C_C") (pintype "passive"))
      (node (ref "R12") (pin "2") (pinfunction "2_2") (pintype "passive"))
    )
    (net (code "60") (name "Net-(LED2-PadC)") (class "Default")
      (node (ref "LED2") (pin "C") (pinfunction "C_C") (pintype "passive"))
      (node (ref "R13") (pin "2") (pinfunction "2_2") (pintype "passive"))
    )
    (net (code "61") (name "Net-(LED3-PadA)") (class "Default")
      (node (ref "LED3") (pin "A") (pinfunction "A_A") (pintype "passive"))
      (node (ref "R7") (pin "2") (pinfunction "2_2") (pintype "passive"))
    )
    (net (code "62") (name "Net-(R1-Pad1)") (class "Default")
      (node (ref "R1") (pin "1") (pinfunction "1_1") (pintype "passive"))
      (node (ref "X1") (pin "3") (pinfunction "3_3") (pintype "passive"))
    )
    (net (code "63") (name "Net-(R2-Pad1)") (class "Default")
      (node (ref "R2") (pin "1") (pinfunction "1_1") (pintype "passive"))
      (node (ref "X1") (pin "2") (pinfunction "2_2") (pintype "passive"))
    )
    (net (code "64") (name "Net-(R3-Pad1)") (class "Default")
      (node (ref "R3") (pin "1") (pinfunction "1_1") (pintype "passive"))
      (node (ref "TRS1") (pin "5") (pinfunction "5_5") (pintype "bidirectional"))
    )
    (net (code "65") (name "Net-(R4-Pad1)") (class "Default")
      (node (ref "R4") (pin "1") (pinfunction "1_1") (pintype "passive"))
      (node (ref "TRS1") (pin "2") (pinfunction "2_2") (pintype "bidirectional"))
    )
    (net (code "66") (name "Net-(R5-Pad1)") (class "Default")
      (node (ref "R5") (pin "1") (pinfunction "1_1") (pintype "passive"))
      (node (ref "SWD") (pin "4") (pinfunction "4_4") (pintype "passive"))
    )
    (net (code "67") (name "Net-(T1-1)") (class "Default")
      (node (ref "D3") (pin "A") (pinfunction "A_A") (pintype "passive"))
      (node (ref "T1") (pin "P$1") (pinfunction "1_P$1") (pintype "passive"))
    )
    (net (code "68") (name "Net-(WIFI-GPIO15)") (class "Default")
      (node (ref "R14") (pin "1") (pinfunction "1_1") (pintype "passive"))
      (node (ref "WIFI") (pin "16") (pinfunction "GPIO15_16") (pintype "bidirectional"))
    )
    (net (code "69") (name "unconnected-(BT-PIO2-Pad14)") (class "Default")
      (node (ref "BT") (pin "14") (pinfunction "PIO2_14") (pintype "bidirectional"))
    )
    (net (code "70") (name "unconnected-(BT-PIO3-Pad13)") (class "Default")
      (node (ref "BT") (pin "13") (pinfunction "PIO3_13") (pintype "bidirectional"))
    )
    (net (code "71") (name "unconnected-(BT-UART_CTS-Pad3)") (class "Default")
      (node (ref "BT") (pin "3") (pinfunction "UART_CTS_3") (pintype "bidirectional"))
    )
    (net (code "72") (name "unconnected-(BT-UART_RTS-Pad1)") (class "Default")
      (node (ref "BT") (pin "1") (pinfunction "UART_RTS_1") (pintype "bidirectional"))
    )
    (net (code "73") (name "unconnected-(IC1A-PA8-Pad29)") (class "Default")
      (node (ref "IC1") (pin "29") (pinfunction "PA8_29") (pintype "bidirectional"))
    )
    (net (code "74") (name "unconnected-(IC1A-PB5-Pad41)") (class "Default")
      (node (ref "IC1") (pin "41") (pinfunction "PB5_41") (pintype "bidirectional"))
    )
    (net (code "75") (name "unconnected-(IC1A-PB12-Pad25)") (class "Default")
      (node (ref "IC1") (pin "25") (pinfunction "PB12_25") (pintype "bidirectional"))
    )
    (net (code "76") (name "unconnected-(WIFI-ADC-Pad2)") (class "Default")
      (node (ref "WIFI") (pin "2") (pinfunction "ADC_2") (pintype "bidirectional"))
    )
    (net (code "77") (name "unconnected-(WIFI-CS0-Pad9)") (class "Default")
      (node (ref "WIFI") (pin "9") (pinfunction "CS0_9") (pintype "bidirectional"))
    )
    (net (code "78") (name "unconnected-(WIFI-GPIO4-Pad19)") (class "Default")
      (node (ref "WIFI") (pin "19") (pinfunction "GPIO4_19") (pintype "bidirectional"))
    )
    (net (code "79") (name "unconnected-(WIFI-GPIO5-Pad20)") (class "Default")
      (node (ref "WIFI") (pin "20") (pinfunction "GPIO5_20") (pintype "bidirectional"))
    )
    (net (code "80") (name "unconnected-(WIFI-GPIO12-Pad6)") (class "Default")
      (node (ref "WIFI") (pin "6") (pinfunction "GPIO12_6") (pintype "bidirectional"))
    )
    (net (code "81") (name "unconnected-(WIFI-GPIO13-Pad7)") (class "Default")
      (node (ref "WIFI") (pin "7") (pinfunction "GPIO13_7") (pintype "bidirectional"))
    )
    (net (code "82") (name "unconnected-(WIFI-GPIO14-Pad5)") (class "Default")
      (node (ref "WIFI") (pin "5") (pinfunction "GPIO14_5") (pintype "bidirectional"))
    )
    (net (code "83") (name "unconnected-(WIFI-GPIO16-Pad4)") (class "Default")
      (node (ref "WIFI") (pin "4") (pinfunction "GPIO16_4") (pintype "bidirectional"))
    )
    (net (code "84") (name "unconnected-(WIFI-IO9-Pad11)") (class "Default")
      (node (ref "WIFI") (pin "11") (pinfunction "IO9_11") (pintype "bidirectional"))
    )
    (net (code "85") (name "unconnected-(WIFI-IO10-Pad12)") (class "Default")
      (node (ref "WIFI") (pin "12") (pinfunction "IO10_12") (pintype "bidirectional"))
    )
    (net (code "86") (name "unconnected-(WIFI-MISO-Pad10)") (class "Default")
      (node (ref "WIFI") (pin "10") (pinfunction "MISO_10") (pintype "bidirectional"))
    )
    (net (code "87") (name "unconnected-(WIFI-MOSI-Pad13)") (class "Default")
      (node (ref "WIFI") (pin "13") (pinfunction "MOSI_13") (pintype "bidirectional"))
    )
    (net (code "88") (name "unconnected-(WIFI-SCLK-Pad14)") (class "Default")
      (node (ref "WIFI") (pin "14") (pinfunction "SCLK_14") (pintype "bidirectional"))
    )
    (net (code "89") (name "unconnected-(X1-Pad4)") (class "Default")
      (node (ref "X1") (pin "4") (pinfunction "4_4") (pintype "passive"))
    )
  )
)
